# SAM4N_Xplained_Pro_dual_input_power_supp.net
KiCad netlist of a schematic drawn in Altium Designer
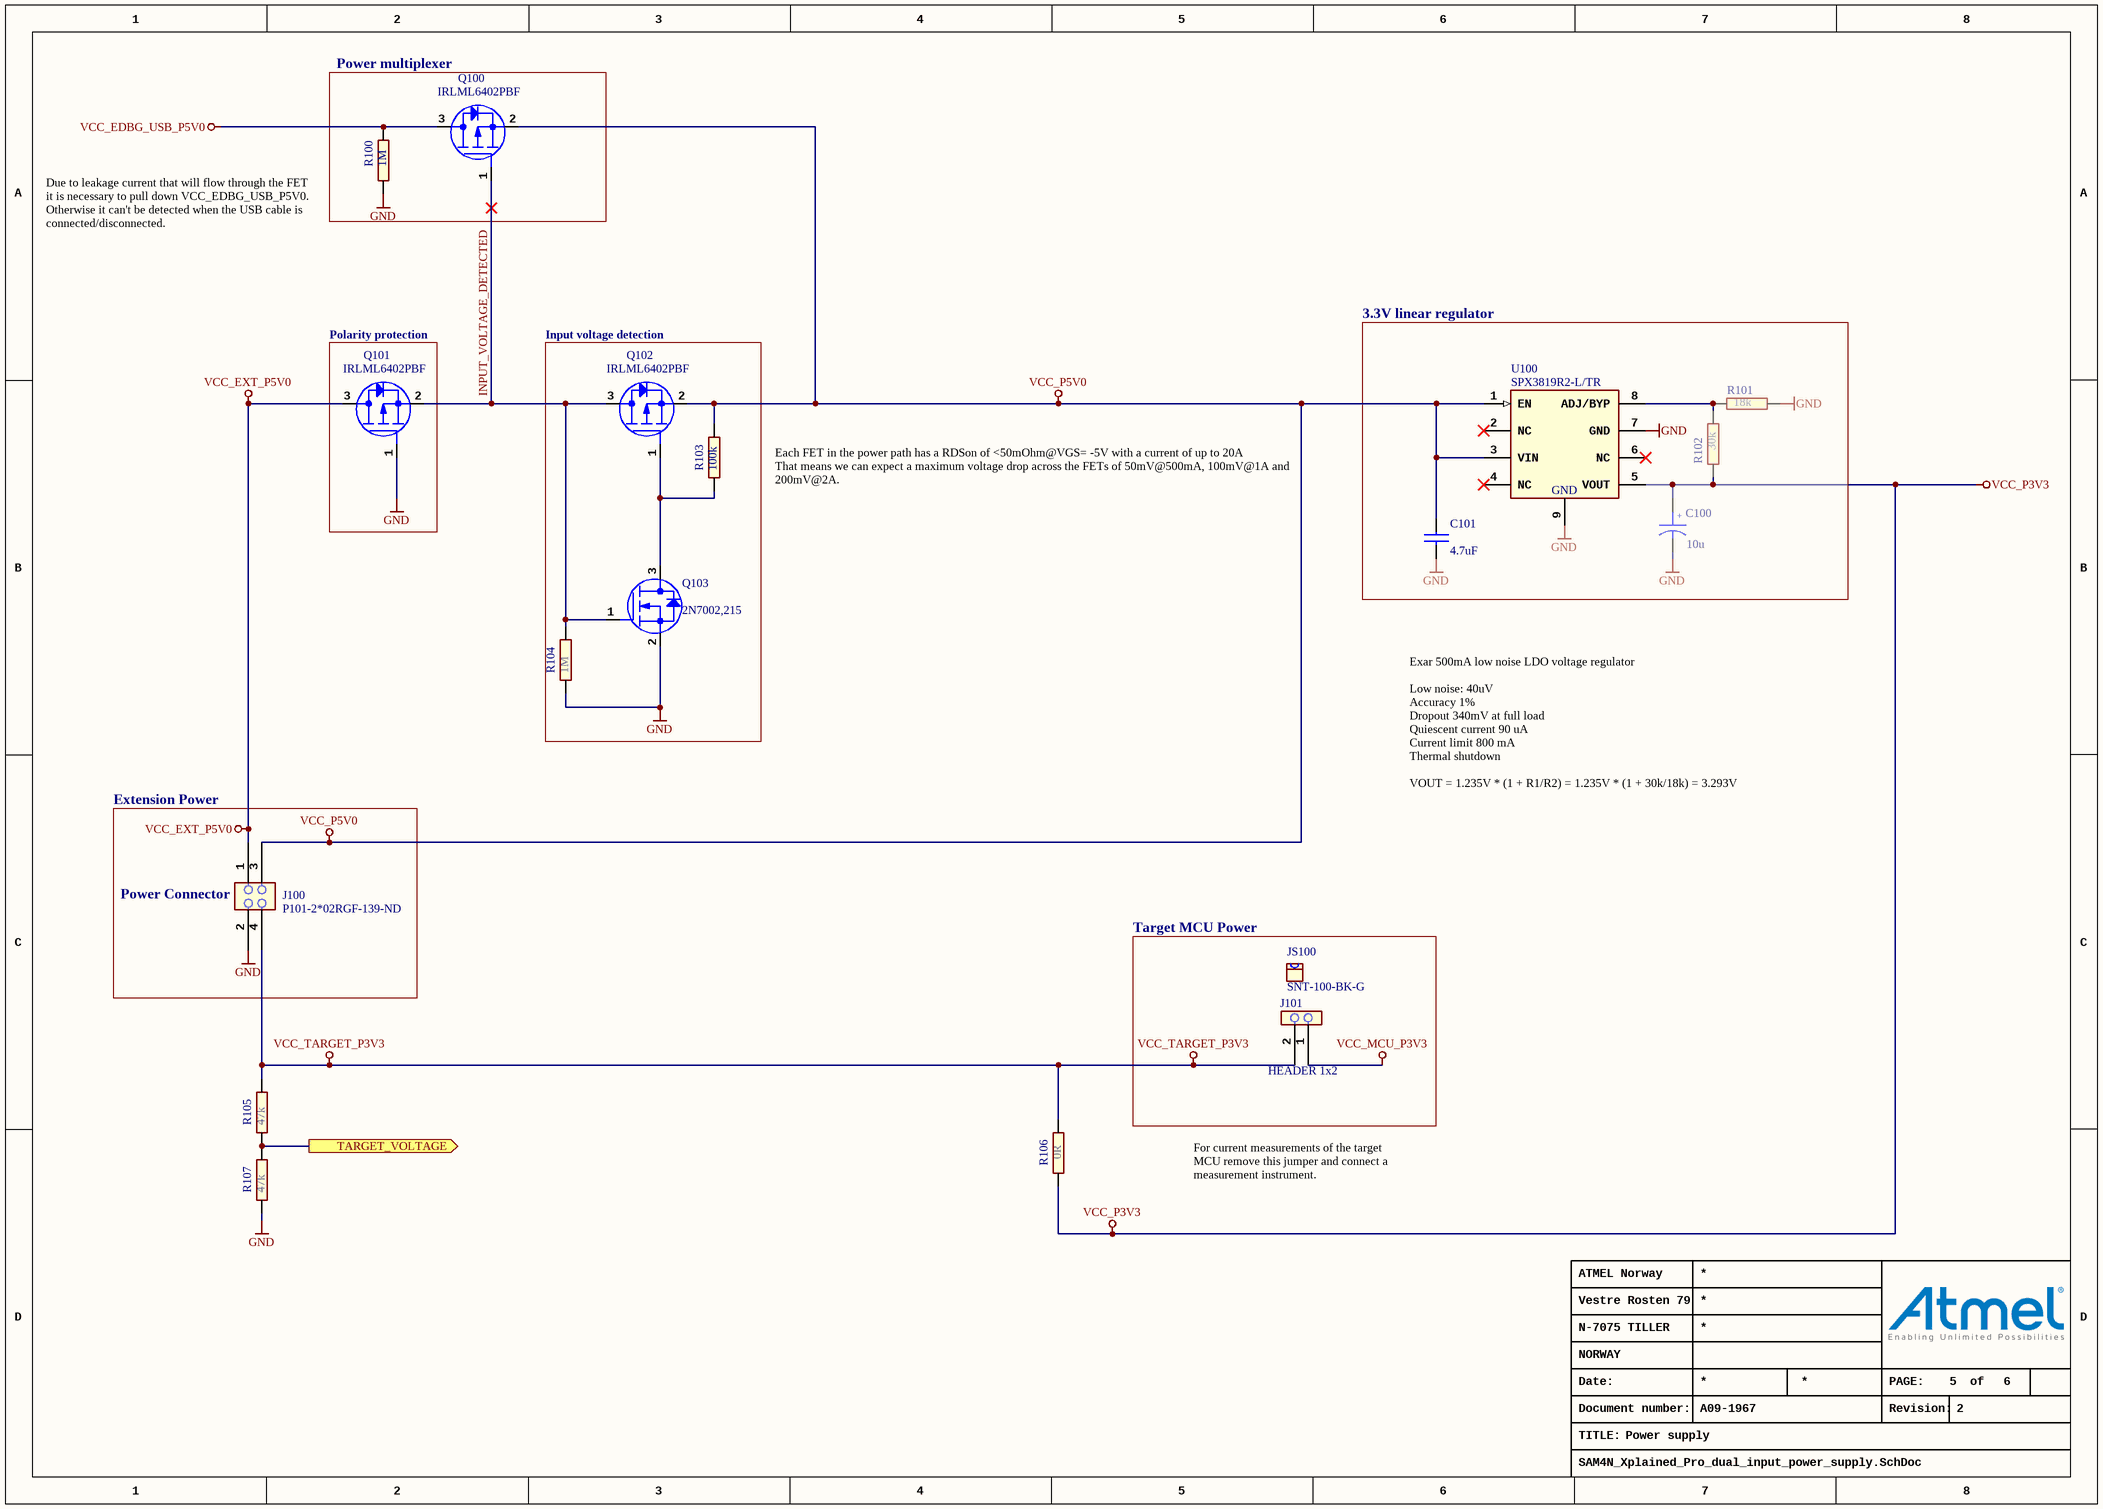
[diagram p0: SAM4N_Xplained_Pro_dual_input_power_supply.SchDoc]

(export (version "E")
  (design (tool "Eeschema 10.0.6"))
  (components
    (comp (ref "C100")
      (value "10u")
      (footprint "AP1-00036")
      (description "SMD tantalum capacitor, ESR = 1.7, 3216-18 (EIA) 1206,")
      (fields (field (name "TOLERANCE") "+-10%") (field (name "MANUFACTURER") "vishay"))
      (libsource (lib "AltiumDbLib") (part "CAP-POL"))
    )
    (comp (ref "C101")
      (value "4.7uF")
      (footprint "AP1-00039")
      (description "Ceramic capacitor, SMD 0603, X5R, 10V, 10% (de31036)")
      (fields (field (name "TOLERANCE") "10%") (field (name "MANUFACTURER") "tdk"))
      (libsource (lib "AltiumDbLib") (part "CAP-NONPOL"))
    )
    (comp (ref "J100")
      (value "P101-2*02RGF-139-ND")
      (footprint "AP8-00628")
      (description "Pin header, 2x2, Right Angle, 2.54mm, THT, Pin In Paste")
      (fields (field (name "Comment") "HEADER 2x2"))
      (libsource (lib "AltiumDbLib") (part "HEADER 2x2"))
    )
    (comp (ref "J101")
      (value "HEADER 1x2")
      (footprint "AP8-00367")
      (description "1x2 pin header, right angle, 2.54 mm pitch, through-hole")
      (fields (field (name "MANUFACTURER") "Pro-data International Corp") (field (name "MPN") "2213R-2G"))
      (libsource (lib "AltiumDbLib") (part "HEADER 1x2"))
    )
    (comp (ref "JS100")
      (value "SNT-100-BK-G")
      (footprint "AP8-00525")
      (description "Jumper cap for 2.54mm pinheader")
      (fields (field (name "MANUFACTURER") "SAMTEC"))
      (libsource (lib "AltiumDbLib") (part "JUMPER_CAP"))
    )
    (comp (ref "Q100")
      (value "IRLML6402PBF")
      (footprint "AP5-00002")
      (description "P-ch. MOSFET. -30V, -3.7A continuous,RDS(ON)=0.05Ohm@VGS=-4,5V, RDS(ON)=0.08Ohm@VGS=-2.5V")
      (fields (field (name "MANUFACTURER") "International Rectifier") (field (name "Comment") "MOSFET_P_GSD"))
      (libsource (lib "AltiumDbLib") (part "MOSFET_P_GSD"))
    )
    (comp (ref "Q101")
      (value "IRLML6402PBF")
      (footprint "AP5-00002")
      (description "P-ch. MOSFET. -30V, -3.7A continuous,RDS(ON)=0.05Ohm@VGS=-4,5V, RDS(ON)=0.08Ohm@VGS=-2.5V")
      (fields (field (name "MANUFACTURER") "International Rectifier") (field (name "Comment") "MOSFET_P_GSD"))
      (libsource (lib "AltiumDbLib") (part "MOSFET_P_GSD"))
    )
    (comp (ref "Q102")
      (value "IRLML6402PBF")
      (footprint "AP5-00002")
      (description "P-ch. MOSFET. -30V, -3.7A continuous,RDS(ON)=0.05Ohm@VGS=-4,5V, RDS(ON)=0.08Ohm@VGS=-2.5V")
      (fields (field (name "MANUFACTURER") "International Rectifier") (field (name "Comment") "MOSFET_P_GSD"))
      (libsource (lib "AltiumDbLib") (part "MOSFET_P_GSD"))
    )
    (comp (ref "Q103")
      (value "2N7002,215")
      (footprint "AP5-00002")
      (description "N-Channel MOSFET. 60V, 0.300A continuous, 1.2A Peak. RDS(ON) = 3.8Ohm@VGS=4.5V, VGS(th)<2.5V")
      (fields (field (name "MANUFACTURER") "NXP") (field (name "Comment") "MOSFET_N_GSD"))
      (libsource (lib "AltiumDbLib") (part "MOSFET_N_GSD"))
    )
    (comp (ref "R100")
      (value "1M")
      (footprint "AP2-00000")
      (description "Thick film resistor, SMD 0402, 1/16W, 1%")
      (fields (field (name "TOLERANCE") "1 %") (field (name "MANUFACTURER") "KOA"))
      (libsource (lib "AltiumDbLib") (part "R2"))
    )
    (comp (ref "R101")
      (value "18k")
      (footprint "AP2-00000")
      (description "Thick film resistor, SMD 0402, 1/16W, 1%")
      (fields (field (name "TOLERANCE") "1 %") (field (name "Comment") "R2"))
      (libsource (lib "") (part "R2_2"))
    )
    (comp (ref "R102")
      (value "30k")
      (footprint "AP2-00000")
      (description "Thick film resistor, SMD 0402, 1/16W, 1%")
      (fields (field (name "TOLERANCE") "1 %") (field (name "Comment") "R2"))
      (libsource (lib "AltiumDbLib") (part "R2"))
    )
    (comp (ref "R103")
      (value "100k")
      (footprint "AP2-00000")
      (description "Thick film resistor, SMD 0402, 1/16W, 1%")
      (fields (field (name "TOLERANCE") "1 %") (field (name "Comment") "R2"))
      (libsource (lib "AltiumDbLib") (part "R2"))
    )
    (comp (ref "R104")
      (value "1M")
      (footprint "AP2-00000")
      (description "Thick film resistor, SMD 0402, 1/16W, 1%")
      (fields (field (name "TOLERANCE") "1 %") (field (name "Comment") "R2"))
      (libsource (lib "AltiumDbLib") (part "R2"))
    )
    (comp (ref "R105")
      (value "47k")
      (footprint "AP2-00000")
      (description "Thick film resistor, SMD 0402, 1/16W, 1%")
      (fields (field (name "TOLERANCE") "1 %") (field (name "Comment") "R2"))
      (libsource (lib "") (part "R2_1"))
    )
    (comp (ref "R106")
      (value "0R")
      (footprint "AP2-00000")
      (description "Thick film resistor, SMD 0402, 1/16W, 1%")
      (fields (field (name "TOLERANCE") "1 %") (field (name "Comment") "R2"))
      (libsource (lib "AltiumDbLib") (part "R2"))
    )
    (comp (ref "R107")
      (value "47k")
      (footprint "AP2-00000")
      (description "Thick film resistor, SMD 0402, 1/16W, 1%")
      (fields (field (name "TOLERANCE") "1 %") (field (name "Comment") "R2"))
      (libsource (lib "") (part "R2_1"))
    )
    (comp (ref "U100")
      (value "SPX3819R2-L/TR")
      (footprint "AP6-00338")
      (description "500mA LDO, ADJ, low noise, 8-DFN package")
      (fields (field (name "TOLERANCE") "±1%") (field (name "MANUFACTURER") "Exar"))
      (libsource (lib "AltiumDbLib") (part "SPX3819R2-L"))
    )
  )
  (nets
    (net (code "1") (name "/INPUT_VOLTAGE_DETECTED") (class "Default")
      (node (ref "Q100") (pin "1") (pinfunction "G_1") (pintype "passive"))
      (node (ref "Q101") (pin "2") (pinfunction "S_2") (pintype "passive"))
      (node (ref "Q102") (pin "3") (pinfunction "D_3") (pintype "passive"))
      (node (ref "Q103") (pin "1") (pinfunction "G_1") (pintype "passive"))
      (node (ref "R104") (pin "2") (pinfunction "2_2") (pintype "passive"))
    )
    (net (code "2") (name "/TARGET_VOLTAGE") (class "Default")
      (node (ref "R105") (pin "1") (pinfunction "1_1") (pintype "passive"))
      (node (ref "R107") (pin "2") (pinfunction "2_2") (pintype "passive"))
    )
    (net (code "3") (name "GND") (class "Default")
      (node (ref "C100") (pin "2") (pinfunction "2_2") (pintype "passive"))
      (node (ref "C101") (pin "2") (pinfunction "2_2") (pintype "passive"))
      (node (ref "J100") (pin "2") (pinfunction "2_2") (pintype "passive"))
      (node (ref "Q101") (pin "1") (pinfunction "G_1") (pintype "passive"))
      (node (ref "Q103") (pin "2") (pinfunction "S_2") (pintype "passive"))
      (node (ref "R100") (pin "1") (pinfunction "1_1") (pintype "passive"))
      (node (ref "R101") (pin "2") (pinfunction "2_2") (pintype "passive"))
      (node (ref "R104") (pin "1") (pinfunction "1_1") (pintype "passive"))
      (node (ref "R107") (pin "1") (pinfunction "1_1") (pintype "passive"))
      (node (ref "U100") (pin "7") (pinfunction "GND_7") (pintype "power_in"))
      (node (ref "U100") (pin "9") (pinfunction "GND_9") (pintype "power_in"))
    )
    (net (code "4") (name "Net-(Q102-G)") (class "Default")
      (node (ref "Q102") (pin "1") (pinfunction "G_1") (pintype "passive"))
      (node (ref "Q103") (pin "3") (pinfunction "D_3") (pintype "passive"))
      (node (ref "R103") (pin "1") (pinfunction "1_1") (pintype "passive"))
    )
    (net (code "5") (name "Net-(U100-ADJ{slash}BYP)") (class "Default")
      (node (ref "R101") (pin "1") (pinfunction "1_1") (pintype "passive"))
      (node (ref "R102") (pin "2") (pinfunction "2_2") (pintype "passive"))
      (node (ref "U100") (pin "8") (pinfunction "ADJ/BYP_8") (pintype "passive"))
    )
    (net (code "6") (name "VCC_EDBG_USB_P5V0") (class "Default")
      (node (ref "Q100") (pin "3") (pinfunction "D_3") (pintype "passive"))
      (node (ref "R100") (pin "2") (pinfunction "2_2") (pintype "passive"))
    )
    (net (code "7") (name "VCC_EXT_P5V0") (class "Default")
      (node (ref "J100") (pin "1") (pinfunction "1_1") (pintype "passive"))
      (node (ref "Q101") (pin "3") (pinfunction "D_3") (pintype "passive"))
    )
    (net (code "8") (name "VCC_MCU_P3V3") (class "Default")
      (node (ref "J101") (pin "1") (pinfunction "1_1") (pintype "passive"))
    )
    (net (code "9") (name "VCC_P3V3") (class "Default")
      (node (ref "C100") (pin "1") (pinfunction "1_1") (pintype "passive"))
      (node (ref "R102") (pin "1") (pinfunction "1_1") (pintype "passive"))
      (node (ref "R106") (pin "1") (pinfunction "1_1") (pintype "passive"))
      (node (ref "U100") (pin "5") (pinfunction "VOUT_5") (pintype "power_in"))
    )
    (net (code "10") (name "VCC_P5V0") (class "Default")
      (node (ref "C101") (pin "1") (pinfunction "1_1") (pintype "passive"))
      (node (ref "J100") (pin "3") (pinfunction "3_3") (pintype "passive"))
      (node (ref "Q100") (pin "2") (pinfunction "S_2") (pintype "passive"))
      (node (ref "Q102") (pin "2") (pinfunction "S_2") (pintype "passive"))
      (node (ref "R103") (pin "2") (pinfunction "2_2") (pintype "passive"))
      (node (ref "U100") (pin "1") (pinfunction "EN_1") (pintype "input"))
      (node (ref "U100") (pin "3") (pinfunction "VIN_3") (pintype "power_in"))
    )
    (net (code "11") (name "VCC_TARGET_P3V3") (class "Default")
      (node (ref "J100") (pin "4") (pinfunction "4_4") (pintype "passive"))
      (node (ref "J101") (pin "2") (pinfunction "2_2") (pintype "passive"))
      (node (ref "R105") (pin "2") (pinfunction "2_2") (pintype "passive"))
      (node (ref "R106") (pin "2") (pinfunction "2_2") (pintype "passive"))
    )
    (net (code "12") (name "unconnected-(U100-NC-Pad2)") (class "Default")
      (node (ref "U100") (pin "2") (pinfunction "NC_2") (pintype "passive+no_connect"))
    )
    (net (code "13") (name "unconnected-(U100-NC-Pad4)") (class "Default")
      (node (ref "U100") (pin "4") (pinfunction "NC_4") (pintype "passive+no_connect"))
    )
    (net (code "14") (name "unconnected-(U100-NC-Pad6)") (class "Default")
      (node (ref "U100") (pin "6") (pinfunction "NC_6") (pintype "passive+no_connect"))
    )
  )
)
